# Score_controller.net
KiCad netlist of a schematic drawn in EAGLE
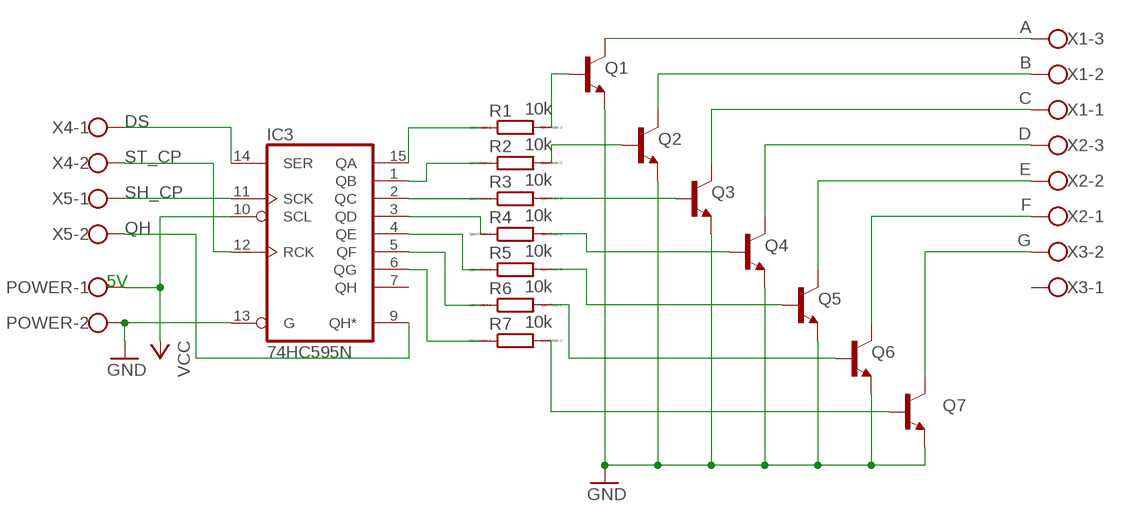
[diagram p0: schematic, sheet 1]

(export (version "E")
  (design (tool "Eeschema 10.0.6"))
  (components
    (comp (ref "IC3")
      (value "74HC595N")
      (footprint "eagle-import:DIL16")
      (libsource (lib "eagle-import") (part "74595NHC"))
    )
    (comp (ref "POWER")
      (value "W237-102")
      (footprint "eagle-import:W237-102")
      (fields (field (name "MPN") "237-102"))
      (libsource (lib "eagle-import") (part "W237-102"))
    )
    (comp (ref "Q1")
      (value "BC338-40")
      (footprint "eagle-import:TO92-EBC")
      (libsource (lib "eagle-import") (part "BC338-40"))
    )
    (comp (ref "Q2")
      (value "BC338-40")
      (footprint "eagle-import:TO92-EBC")
      (libsource (lib "eagle-import") (part "BC338-40"))
    )
    (comp (ref "Q3")
      (value "BC338-40")
      (footprint "eagle-import:TO92-EBC")
      (libsource (lib "eagle-import") (part "BC338-40"))
    )
    (comp (ref "Q4")
      (value "BC338-40")
      (footprint "eagle-import:TO92-EBC")
      (libsource (lib "eagle-import") (part "BC338-40"))
    )
    (comp (ref "Q5")
      (value "BC338-40")
      (footprint "eagle-import:TO92-EBC")
      (libsource (lib "eagle-import") (part "BC338-40"))
    )
    (comp (ref "Q6")
      (value "BC338-40")
      (footprint "eagle-import:TO92-EBC")
      (libsource (lib "eagle-import") (part "BC338-40"))
    )
    (comp (ref "Q7")
      (value "BC338-40")
      (footprint "eagle-import:TO92-EBC")
      (libsource (lib "eagle-import") (part "BC338-40"))
    )
    (comp (ref "R1")
      (value "10k")
      (footprint "eagle-import:0204_7")
      (libsource (lib "eagle-import") (part "R0204/7"))
    )
    (comp (ref "R2")
      (value "10k")
      (footprint "eagle-import:0204_7")
      (libsource (lib "eagle-import") (part "R0204/7"))
    )
    (comp (ref "R3")
      (value "10k")
      (footprint "eagle-import:0204_7")
      (libsource (lib "eagle-import") (part "R0204/7"))
    )
    (comp (ref "R4")
      (value "10k")
      (footprint "eagle-import:0204_7")
      (libsource (lib "eagle-import") (part "R0204/7"))
    )
    (comp (ref "R5")
      (value "10k")
      (footprint "eagle-import:0204_7")
      (libsource (lib "eagle-import") (part "R0204/7"))
    )
    (comp (ref "R6")
      (value "10k")
      (footprint "eagle-import:0204_7")
      (libsource (lib "eagle-import") (part "R0204/7"))
    )
    (comp (ref "R7")
      (value "10k")
      (footprint "eagle-import:0204_7")
      (libsource (lib "eagle-import") (part "R0204/7"))
    )
    (comp (ref "X1")
      (value "W237-103")
      (footprint "eagle-import:W237-103")
      (fields (field (name "MPN") "237-103"))
      (libsource (lib "eagle-import") (part "W237-103"))
    )
    (comp (ref "X2")
      (value "W237-103")
      (footprint "eagle-import:W237-103")
      (fields (field (name "MPN") "237-103"))
      (libsource (lib "eagle-import") (part "W237-103"))
    )
    (comp (ref "X3")
      (value "W237-102")
      (footprint "eagle-import:W237-102")
      (fields (field (name "MPN") "237-102"))
      (libsource (lib "eagle-import") (part "W237-102"))
    )
    (comp (ref "X4")
      (value "W237-102")
      (footprint "eagle-import:W237-102")
      (fields (field (name "MPN") "237-102"))
      (libsource (lib "eagle-import") (part "W237-102"))
    )
    (comp (ref "X5")
      (value "W237-102")
      (footprint "eagle-import:W237-102")
      (fields (field (name "MPN") "237-102"))
      (libsource (lib "eagle-import") (part "W237-102"))
    )
  )
  (nets
    (net (code "1") (name "/A") (class "Default")
      (node (ref "Q1") (pin "C") (pinfunction "C_C") (pintype "passive"))
      (node (ref "X1") (pin "3") (pinfunction "KL_3") (pintype "passive"))
    )
    (net (code "2") (name "/B") (class "Default")
      (node (ref "Q2") (pin "C") (pinfunction "C_C") (pintype "passive"))
      (node (ref "X1") (pin "2") (pinfunction "KL_2") (pintype "passive"))
    )
    (net (code "3") (name "/C") (class "Default")
      (node (ref "Q3") (pin "C") (pinfunction "C_C") (pintype "passive"))
      (node (ref "X1") (pin "1") (pinfunction "KL_1") (pintype "passive"))
    )
    (net (code "4") (name "/D") (class "Default")
      (node (ref "Q4") (pin "C") (pinfunction "C_C") (pintype "passive"))
      (node (ref "X2") (pin "3") (pinfunction "KL_3") (pintype "passive"))
    )
    (net (code "5") (name "/DS") (class "Default")
      (node (ref "IC3") (pin "14") (pinfunction "SER_14") (pintype "input"))
      (node (ref "X4") (pin "1") (pinfunction "KL_1") (pintype "passive"))
    )
    (net (code "6") (name "/E") (class "Default")
      (node (ref "Q5") (pin "C") (pinfunction "C_C") (pintype "passive"))
      (node (ref "X2") (pin "2") (pinfunction "KL_2") (pintype "passive"))
    )
    (net (code "7") (name "/F") (class "Default")
      (node (ref "Q6") (pin "C") (pinfunction "C_C") (pintype "passive"))
      (node (ref "X2") (pin "1") (pinfunction "KL_1") (pintype "passive"))
    )
    (net (code "8") (name "/G") (class "Default")
      (node (ref "Q7") (pin "C") (pinfunction "C_C") (pintype "passive"))
      (node (ref "X3") (pin "2") (pinfunction "KL_2") (pintype "passive"))
    )
    (net (code "9") (name "/QH") (class "Default")
      (node (ref "IC3") (pin "9") (pinfunction "QH*_9") (pintype "tri_state"))
      (node (ref "X5") (pin "2") (pinfunction "KL_2") (pintype "passive"))
    )
    (net (code "10") (name "/SH_CP") (class "Default")
      (node (ref "IC3") (pin "11") (pinfunction "SCK_11") (pintype "input"))
      (node (ref "X5") (pin "1") (pinfunction "KL_1") (pintype "passive"))
    )
    (net (code "11") (name "/ST_CP") (class "Default")
      (node (ref "IC3") (pin "12") (pinfunction "RCK_12") (pintype "input"))
      (node (ref "X4") (pin "2") (pinfunction "KL_2") (pintype "passive"))
    )
    (net (code "12") (name "GND") (class "Default")
      (node (ref "IC3") (pin "13") (pinfunction "G_13") (pintype "input"))
      (node (ref "POWER") (pin "2") (pinfunction "KL_2") (pintype "passive"))
      (node (ref "Q1") (pin "E") (pinfunction "E_E") (pintype "passive"))
      (node (ref "Q2") (pin "E") (pinfunction "E_E") (pintype "passive"))
      (node (ref "Q3") (pin "E") (pinfunction "E_E") (pintype "passive"))
      (node (ref "Q4") (pin "E") (pinfunction "E_E") (pintype "passive"))
      (node (ref "Q5") (pin "E") (pinfunction "E_E") (pintype "passive"))
      (node (ref "Q6") (pin "E") (pinfunction "E_E") (pintype "passive"))
      (node (ref "Q7") (pin "E") (pinfunction "E_E") (pintype "passive"))
    )
    (net (code "13") (name "Net-(IC3A-QA)") (class "Default")
      (node (ref "IC3") (pin "15") (pinfunction "QA_15") (pintype "tri_state"))
      (node (ref "R1") (pin "1") (pinfunction "1_1") (pintype "passive"))
    )
    (net (code "14") (name "Net-(IC3A-QB)") (class "Default")
      (node (ref "IC3") (pin "1") (pinfunction "QB_1") (pintype "tri_state"))
      (node (ref "R2") (pin "1") (pinfunction "1_1") (pintype "passive"))
    )
    (net (code "15") (name "Net-(IC3A-QC)") (class "Default")
      (node (ref "IC3") (pin "2") (pinfunction "QC_2") (pintype "tri_state"))
      (node (ref "R3") (pin "1") (pinfunction "1_1") (pintype "passive"))
    )
    (net (code "16") (name "Net-(IC3A-QD)") (class "Default")
      (node (ref "IC3") (pin "3") (pinfunction "QD_3") (pintype "tri_state"))
      (node (ref "R4") (pin "1") (pinfunction "1_1") (pintype "passive"))
    )
    (net (code "17") (name "Net-(IC3A-QE)") (class "Default")
      (node (ref "IC3") (pin "4") (pinfunction "QE_4") (pintype "tri_state"))
      (node (ref "R5") (pin "1") (pinfunction "1_1") (pintype "passive"))
    )
    (net (code "18") (name "Net-(IC3A-QF)") (class "Default")
      (node (ref "IC3") (pin "5") (pinfunction "QF_5") (pintype "tri_state"))
      (node (ref "R6") (pin "1") (pinfunction "1_1") (pintype "passive"))
    )
    (net (code "19") (name "Net-(IC3A-QG)") (class "Default")
      (node (ref "IC3") (pin "6") (pinfunction "QG_6") (pintype "tri_state"))
      (node (ref "R7") (pin "1") (pinfunction "1_1") (pintype "passive"))
    )
    (net (code "20") (name "Net-(Q1-PadB)") (class "Default")
      (node (ref "Q1") (pin "B") (pinfunction "B_B") (pintype "passive"))
      (node (ref "R1") (pin "2") (pinfunction "2_2") (pintype "passive"))
    )
    (net (code "21") (name "Net-(Q2-PadB)") (class "Default")
      (node (ref "Q2") (pin "B") (pinfunction "B_B") (pintype "passive"))
      (node (ref "R2") (pin "2") (pinfunction "2_2") (pintype "passive"))
    )
    (net (code "22") (name "Net-(Q3-PadB)") (class "Default")
      (node (ref "Q3") (pin "B") (pinfunction "B_B") (pintype "passive"))
      (node (ref "R3") (pin "2") (pinfunction "2_2") (pintype "passive"))
    )
    (net (code "23") (name "Net-(Q4-PadB)") (class "Default")
      (node (ref "Q4") (pin "B") (pinfunction "B_B") (pintype "passive"))
      (node (ref "R4") (pin "2") (pinfunction "2_2") (pintype "passive"))
    )
    (net (code "24") (name "Net-(Q5-PadB)") (class "Default")
      (node (ref "Q5") (pin "B") (pinfunction "B_B") (pintype "passive"))
      (node (ref "R5") (pin "2") (pinfunction "2_2") (pintype "passive"))
    )
    (net (code "25") (name "Net-(Q6-PadB)") (class "Default")
      (node (ref "Q6") (pin "B") (pinfunction "B_B") (pintype "passive"))
      (node (ref "R6") (pin "2") (pinfunction "2_2") (pintype "passive"))
    )
    (net (code "26") (name "Net-(Q7-PadB)") (class "Default")
      (node (ref "Q7") (pin "B") (pinfunction "B_B") (pintype "passive"))
      (node (ref "R7") (pin "2") (pinfunction "2_2") (pintype "passive"))
    )
    (net (code "27") (name "VCC") (class "Default")
      (node (ref "IC3") (pin "10") (pinfunction "SCL_10") (pintype "input"))
      (node (ref "POWER") (pin "1") (pinfunction "KL_1") (pintype "passive"))
    )
    (net (code "28") (name "unconnected-(IC3A-QH-Pad7)") (class "Default")
      (node (ref "IC3") (pin "7") (pinfunction "QH_7") (pintype "tri_state"))
    )
    (net (code "29") (name "unconnected-(X3A-KL-Pad1)") (class "Default")
      (node (ref "X3") (pin "1") (pinfunction "KL_1") (pintype "passive"))
    )
  )
)
